# pcm2912a.net
KiCad netlist of a schematic drawn in EAGLE
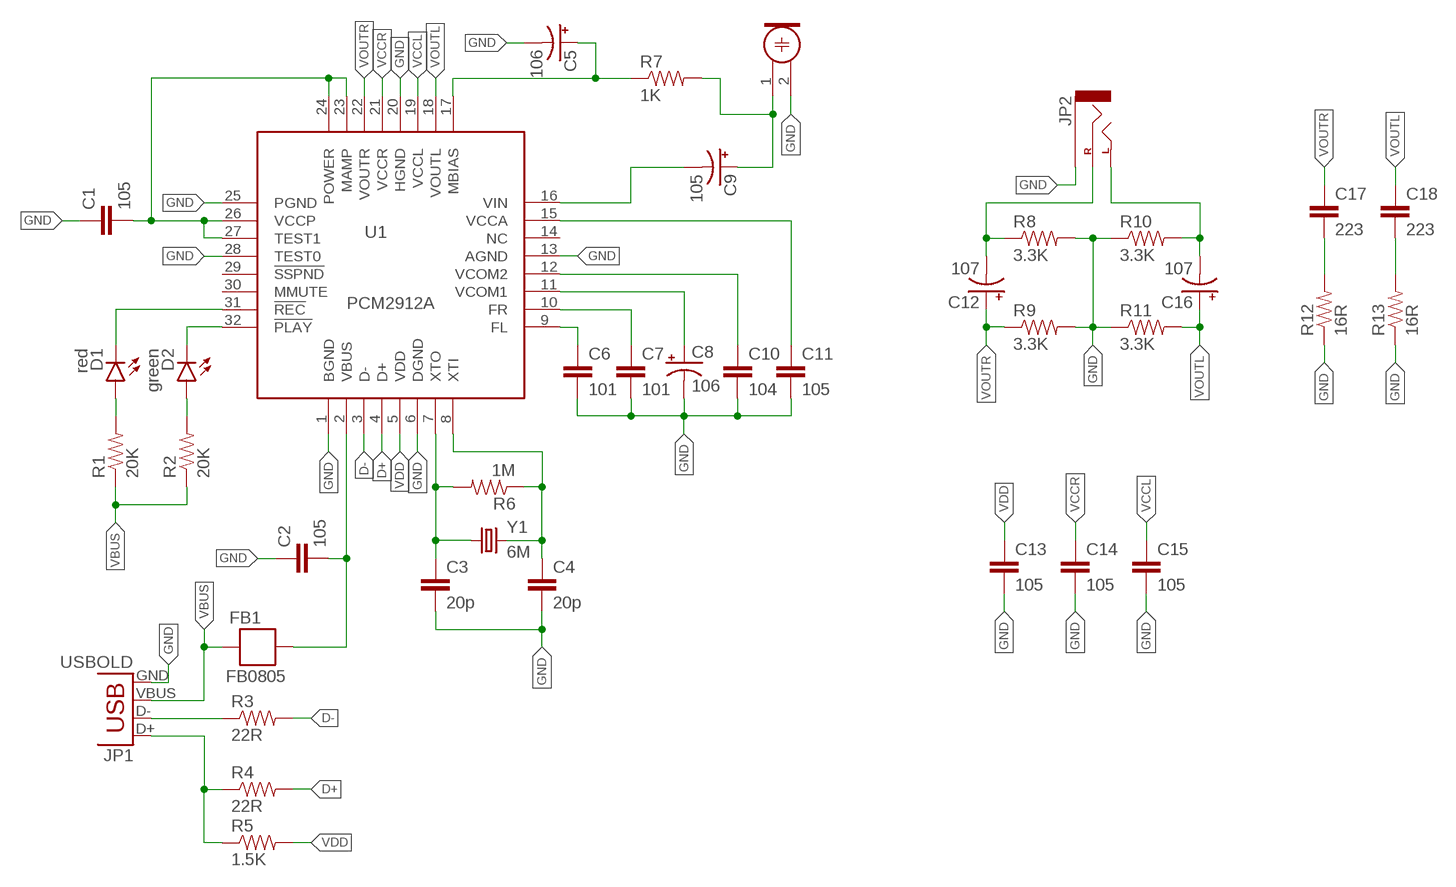
[diagram p0: schematic, sheet 1]

(export (version "E")
  (design (tool "Eeschema 10.0.6"))
  (components
    (comp (ref "C1")
      (value "105")
      (footprint "eagle-import:0402-CAP")
      (libsource (lib "eagle-import") (part "CAP0402-CAP"))
    )
    (comp (ref "C2")
      (value "105")
      (footprint "eagle-import:0402-CAP")
      (libsource (lib "eagle-import") (part "CAP0402-CAP"))
    )
    (comp (ref "C3")
      (value "20p")
      (footprint "eagle-import:0402-CAP")
      (libsource (lib "eagle-import") (part "CAP0402-CAP"))
    )
    (comp (ref "C4")
      (value "20p")
      (footprint "eagle-import:0402-CAP")
      (libsource (lib "eagle-import") (part "CAP0402-CAP"))
    )
    (comp (ref "C5")
      (value "106")
      (footprint "eagle-import:EIA3216-KIT")
      (libsource (lib "eagle-import") (part "CAP_POL1206-KIT"))
    )
    (comp (ref "C6")
      (value "101")
      (footprint "eagle-import:0402-CAP")
      (libsource (lib "eagle-import") (part "CAP0402-CAP"))
    )
    (comp (ref "C7")
      (value "101")
      (footprint "eagle-import:0402-CAP")
      (libsource (lib "eagle-import") (part "CAP0402-CAP"))
    )
    (comp (ref "C8")
      (value "106")
      (footprint "eagle-import:EIA3216-KIT")
      (libsource (lib "eagle-import") (part "CAP_POL1206-KIT"))
    )
    (comp (ref "C9")
      (value "105")
      (footprint "eagle-import:EIA3216-KIT")
      (libsource (lib "eagle-import") (part "CAP_POL1206-KIT"))
    )
    (comp (ref "C10")
      (value "104")
      (footprint "eagle-import:0402-CAP")
      (libsource (lib "eagle-import") (part "CAP0402-CAP"))
    )
    (comp (ref "C11")
      (value "105")
      (footprint "eagle-import:0402-CAP")
      (libsource (lib "eagle-import") (part "CAP0402-CAP"))
    )
    (comp (ref "C12")
      (value "107")
      (footprint "eagle-import:EIA3528-KIT")
      (libsource (lib "eagle-import") (part "CAP_POL3528-KIT"))
    )
    (comp (ref "C13")
      (value "105")
      (footprint "eagle-import:0402-CAP")
      (libsource (lib "eagle-import") (part "CAP0402-CAP"))
    )
    (comp (ref "C14")
      (value "105")
      (footprint "eagle-import:0402-CAP")
      (libsource (lib "eagle-import") (part "CAP0402-CAP"))
    )
    (comp (ref "C15")
      (value "105")
      (footprint "eagle-import:0402-CAP")
      (libsource (lib "eagle-import") (part "CAP0402-CAP"))
    )
    (comp (ref "C16")
      (value "107")
      (footprint "eagle-import:EIA3528-KIT")
      (libsource (lib "eagle-import") (part "CAP_POL3528-KIT"))
    )
    (comp (ref "C17")
      (value "223")
      (footprint "eagle-import:0402-CAP")
      (libsource (lib "eagle-import") (part "CAP0402-CAP"))
    )
    (comp (ref "C18")
      (value "223")
      (footprint "eagle-import:0402-CAP")
      (libsource (lib "eagle-import") (part "CAP0402-CAP"))
    )
    (comp (ref "D1")
      (value "red")
      (footprint "eagle-import:LED-0603-EASY")
      (libsource (lib "eagle-import") (part "LED-EASY"))
    )
    (comp (ref "D2")
      (value "green")
      (footprint "eagle-import:LED-0603-EASY")
      (libsource (lib "eagle-import") (part "LED-EASY"))
    )
    (comp (ref "FB1")
      (value "FB0805")
      (footprint "eagle-import:0805")
      (libsource (lib "eagle-import") (part "FB0805"))
    )
    (comp (ref "JP1")
      (value "USBOLD")
      (footprint "eagle-import:USB-MINIB-OLD")
      (libsource (lib "eagle-import") (part "USBOLD"))
    )
    (comp (ref "JP2")
      (value "AUDIO-JACKAUDIO-JACK-3.5MM-PTH-JLC")
      (footprint "eagle-import:AUDIO-JACK-3.5MM-PTH-JLC")
      (libsource (lib "eagle-import") (part "AUDIO-JACKAUDIO-JACK-3.5MM-PTH-JLC"))
    )
    (comp (ref "M1")
      (value "ELECTRET_MICROPHON-WM-62PC/62PK")
      (footprint "eagle-import:WM-62PC_62PK")
      (libsource (lib "eagle-import") (part "ELECTRET_MICROPHON-WM-62PC/62PK"))
    )
    (comp (ref "R1")
      (value "20K")
      (footprint "eagle-import:0402-RES")
      (libsource (lib "eagle-import") (part "RESISTOR0402"))
    )
    (comp (ref "R2")
      (value "20K")
      (footprint "eagle-import:0402-RES")
      (libsource (lib "eagle-import") (part "RESISTOR0402"))
    )
    (comp (ref "R3")
      (value "22R")
      (footprint "eagle-import:0402-RES")
      (libsource (lib "eagle-import") (part "RESISTOR0402"))
    )
    (comp (ref "R4")
      (value "22R")
      (footprint "eagle-import:0402-RES")
      (libsource (lib "eagle-import") (part "RESISTOR0402"))
    )
    (comp (ref "R5")
      (value "1.5K")
      (footprint "eagle-import:0402-RES")
      (libsource (lib "eagle-import") (part "RESISTOR0402"))
    )
    (comp (ref "R6")
      (value "1M")
      (footprint "eagle-import:0402-RES")
      (libsource (lib "eagle-import") (part "RESISTOR0402"))
    )
    (comp (ref "R7")
      (value "1K")
      (footprint "eagle-import:0402-RES")
      (libsource (lib "eagle-import") (part "RESISTOR0402"))
    )
    (comp (ref "R8")
      (value "3.3K")
      (footprint "eagle-import:0402-RES")
      (libsource (lib "eagle-import") (part "RESISTOR0402"))
    )
    (comp (ref "R9")
      (value "3.3K")
      (footprint "eagle-import:0402-RES")
      (libsource (lib "eagle-import") (part "RESISTOR0402"))
    )
    (comp (ref "R10")
      (value "3.3K")
      (footprint "eagle-import:0402-RES")
      (libsource (lib "eagle-import") (part "RESISTOR0402"))
    )
    (comp (ref "R11")
      (value "3.3K")
      (footprint "eagle-import:0402-RES")
      (libsource (lib "eagle-import") (part "RESISTOR0402"))
    )
    (comp (ref "R12")
      (value "16R")
      (footprint "eagle-import:0402-RES")
      (libsource (lib "eagle-import") (part "RESISTOR0402"))
    )
    (comp (ref "R13")
      (value "16R")
      (footprint "eagle-import:0402-RES")
      (libsource (lib "eagle-import") (part "RESISTOR0402"))
    )
    (comp (ref "U1")
      (value "PCM2912A")
      (footprint "eagle-import:TQFP32-08")
      (libsource (lib "eagle-import") (part "PCM2912A"))
    )
    (comp (ref "Y1")
      (value "6M")
      (footprint "eagle-import:HC49US")
      (libsource (lib "eagle-import") (part "CRYSTALHC49US"))
    )
  )
  (nets
    (net (code "1") (name "D+") (class "Default")
      (node (ref "R4") (pin "2") (pinfunction "2_2") (pintype "passive"))
      (node (ref "U1") (pin "4") (pinfunction "D+_4") (pintype "bidirectional"))
    )
    (net (code "2") (name "D-") (class "Default")
      (node (ref "R3") (pin "2") (pinfunction "2_2") (pintype "passive"))
      (node (ref "U1") (pin "3") (pinfunction "D-_3") (pintype "bidirectional"))
    )
    (net (code "3") (name "GND") (class "Default")
      (node (ref "C1") (pin "1") (pinfunction "1_1") (pintype "passive"))
      (node (ref "C10") (pin "2") (pinfunction "2_2") (pintype "passive"))
      (node (ref "C11") (pin "2") (pinfunction "2_2") (pintype "passive"))
      (node (ref "C13") (pin "2") (pinfunction "2_2") (pintype "passive"))
      (node (ref "C14") (pin "2") (pinfunction "2_2") (pintype "passive"))
      (node (ref "C15") (pin "2") (pinfunction "2_2") (pintype "passive"))
      (node (ref "C2") (pin "1") (pinfunction "1_1") (pintype "passive"))
      (node (ref "C3") (pin "2") (pinfunction "2_2") (pintype "passive"))
      (node (ref "C4") (pin "2") (pinfunction "2_2") (pintype "passive"))
      (node (ref "C5") (pin "C") (pinfunction "-_C") (pintype "passive"))
      (node (ref "C6") (pin "2") (pinfunction "2_2") (pintype "passive"))
      (node (ref "C7") (pin "2") (pinfunction "2_2") (pintype "passive"))
      (node (ref "C8") (pin "C") (pinfunction "-_C") (pintype "passive"))
      (node (ref "JP1") (pin "GND") (pinfunction "GND_GND") (pintype "bidirectional"))
      (node (ref "JP2") (pin "P$1") (pinfunction "SLEEVE_P$1") (pintype "bidirectional"))
      (node (ref "M1") (pin "2") (pinfunction "2_2") (pintype "passive"))
      (node (ref "R10") (pin "1") (pinfunction "1_1") (pintype "passive"))
      (node (ref "R11") (pin "1") (pinfunction "1_1") (pintype "passive"))
      (node (ref "R12") (pin "1") (pinfunction "1_1") (pintype "passive"))
      (node (ref "R13") (pin "1") (pinfunction "1_1") (pintype "passive"))
      (node (ref "R8") (pin "2") (pinfunction "2_2") (pintype "passive"))
      (node (ref "R9") (pin "2") (pinfunction "2_2") (pintype "passive"))
      (node (ref "U1") (pin "1") (pinfunction "BGND_1") (pintype "bidirectional"))
      (node (ref "U1") (pin "13") (pinfunction "AGND_13") (pintype "bidirectional"))
      (node (ref "U1") (pin "20") (pinfunction "HGND_20") (pintype "bidirectional"))
      (node (ref "U1") (pin "25") (pinfunction "PGND_25") (pintype "bidirectional"))
      (node (ref "U1") (pin "28") (pinfunction "TEST0_28") (pintype "bidirectional"))
      (node (ref "U1") (pin "6") (pinfunction "DGND_6") (pintype "bidirectional"))
    )
    (net (code "4") (name "Net-(C5-+)") (class "Default")
      (node (ref "C5") (pin "A") (pinfunction "+_A") (pintype "passive"))
      (node (ref "R7") (pin "1") (pinfunction "1_1") (pintype "passive"))
      (node (ref "U1") (pin "17") (pinfunction "MBIAS_17") (pintype "bidirectional"))
    )
    (net (code "5") (name "Net-(C8-+)") (class "Default")
      (node (ref "C8") (pin "A") (pinfunction "+_A") (pintype "passive"))
      (node (ref "U1") (pin "11") (pinfunction "VCOM1_11") (pintype "bidirectional"))
    )
    (net (code "6") (name "Net-(C9-+)") (class "Default")
      (node (ref "C9") (pin "A") (pinfunction "+_A") (pintype "passive"))
      (node (ref "M1") (pin "1") (pinfunction "1_1") (pintype "passive"))
      (node (ref "R7") (pin "2") (pinfunction "2_2") (pintype "passive"))
    )
    (net (code "7") (name "Net-(C9--)") (class "Default")
      (node (ref "C9") (pin "C") (pinfunction "-_C") (pintype "passive"))
      (node (ref "U1") (pin "16") (pinfunction "VIN_16") (pintype "bidirectional"))
    )
    (net (code "8") (name "Net-(C12--)") (class "Default")
      (node (ref "C12") (pin "C") (pinfunction "-_C") (pintype "passive"))
      (node (ref "JP2") (pin "P$2") (pinfunction "RIGHT_P$2") (pintype "bidirectional"))
      (node (ref "R8") (pin "1") (pinfunction "1_1") (pintype "passive"))
    )
    (net (code "9") (name "Net-(C16--)") (class "Default")
      (node (ref "C16") (pin "C") (pinfunction "-_C") (pintype "passive"))
      (node (ref "JP2") (pin "P$3") (pinfunction "LEFT_P$3") (pintype "bidirectional"))
      (node (ref "R10") (pin "2") (pinfunction "2_2") (pintype "passive"))
    )
    (net (code "10") (name "Net-(C17-Pad2)") (class "Default")
      (node (ref "C17") (pin "2") (pinfunction "2_2") (pintype "passive"))
      (node (ref "R12") (pin "2") (pinfunction "2_2") (pintype "passive"))
    )
    (net (code "11") (name "Net-(C18-Pad2)") (class "Default")
      (node (ref "C18") (pin "2") (pinfunction "2_2") (pintype "passive"))
      (node (ref "R13") (pin "2") (pinfunction "2_2") (pintype "passive"))
    )
    (net (code "12") (name "Net-(D1-A)") (class "Default")
      (node (ref "D1") (pin "+") (pinfunction "A_+") (pintype "passive"))
      (node (ref "R1") (pin "2") (pinfunction "2_2") (pintype "passive"))
    )
    (net (code "13") (name "Net-(D1-C)") (class "Default")
      (node (ref "D1") (pin "-") (pinfunction "C_-") (pintype "passive"))
      (node (ref "U1") (pin "31") (pinfunction "~{REC}_31") (pintype "bidirectional"))
    )
    (net (code "14") (name "Net-(D2-A)") (class "Default")
      (node (ref "D2") (pin "+") (pinfunction "A_+") (pintype "passive"))
      (node (ref "R2") (pin "2") (pinfunction "2_2") (pintype "passive"))
    )
    (net (code "15") (name "Net-(D2-C)") (class "Default")
      (node (ref "D2") (pin "-") (pinfunction "C_-") (pintype "passive"))
      (node (ref "U1") (pin "32") (pinfunction "~{PLAY}_32") (pintype "bidirectional"))
    )
    (net (code "16") (name "Net-(FB1-P$1)") (class "Default")
      (node (ref "C2") (pin "2") (pinfunction "2_2") (pintype "passive"))
      (node (ref "FB1") (pin "1") (pinfunction "P$1_1") (pintype "bidirectional"))
      (node (ref "U1") (pin "2") (pinfunction "VBUS_2") (pintype "bidirectional"))
    )
    (net (code "17") (name "Net-(JP1-PadD+)") (class "Default")
      (node (ref "JP1") (pin "D+") (pinfunction "D+_D+") (pintype "bidirectional"))
      (node (ref "R4") (pin "1") (pinfunction "1_1") (pintype "passive"))
      (node (ref "R5") (pin "1") (pinfunction "1_1") (pintype "passive"))
    )
    (net (code "18") (name "Net-(JP1-PadD-)") (class "Default")
      (node (ref "JP1") (pin "D-") (pinfunction "D-_D-") (pintype "bidirectional"))
      (node (ref "R3") (pin "1") (pinfunction "1_1") (pintype "passive"))
    )
    (net (code "19") (name "Net-(U1-FL)") (class "Default")
      (node (ref "C6") (pin "1") (pinfunction "1_1") (pintype "passive"))
      (node (ref "U1") (pin "9") (pinfunction "FL_9") (pintype "bidirectional"))
    )
    (net (code "20") (name "Net-(U1-FR)") (class "Default")
      (node (ref "C7") (pin "1") (pinfunction "1_1") (pintype "passive"))
      (node (ref "U1") (pin "10") (pinfunction "FR_10") (pintype "bidirectional"))
    )
    (net (code "21") (name "Net-(U1-MAMP)") (class "Default")
      (node (ref "C1") (pin "2") (pinfunction "2_2") (pintype "passive"))
      (node (ref "U1") (pin "23") (pinfunction "MAMP_23") (pintype "bidirectional"))
      (node (ref "U1") (pin "24") (pinfunction "POWER_24") (pintype "bidirectional"))
      (node (ref "U1") (pin "26") (pinfunction "VCCP_26") (pintype "bidirectional"))
      (node (ref "U1") (pin "27") (pinfunction "TEST1_27") (pintype "bidirectional"))
    )
    (net (code "22") (name "Net-(U1-VCCA)") (class "Default")
      (node (ref "C11") (pin "1") (pinfunction "1_1") (pintype "passive"))
      (node (ref "U1") (pin "15") (pinfunction "VCCA_15") (pintype "bidirectional"))
    )
    (net (code "23") (name "Net-(U1-VCOM2)") (class "Default")
      (node (ref "C10") (pin "1") (pinfunction "1_1") (pintype "passive"))
      (node (ref "U1") (pin "12") (pinfunction "VCOM2_12") (pintype "bidirectional"))
    )
    (net (code "24") (name "Net-(U1-XTI)") (class "Default")
      (node (ref "C4") (pin "1") (pinfunction "1_1") (pintype "passive"))
      (node (ref "R6") (pin "1") (pinfunction "1_1") (pintype "passive"))
      (node (ref "U1") (pin "8") (pinfunction "XTI_8") (pintype "bidirectional"))
      (node (ref "Y1") (pin "2") (pinfunction "2_2") (pintype "passive"))
    )
    (net (code "25") (name "Net-(U1-XTO)") (class "Default")
      (node (ref "C3") (pin "1") (pinfunction "1_1") (pintype "passive"))
      (node (ref "R6") (pin "2") (pinfunction "2_2") (pintype "passive"))
      (node (ref "U1") (pin "7") (pinfunction "XTO_7") (pintype "bidirectional"))
      (node (ref "Y1") (pin "1") (pinfunction "1_1") (pintype "passive"))
    )
    (net (code "26") (name "VBUS") (class "Default")
      (node (ref "FB1") (pin "2") (pinfunction "P$2_2") (pintype "bidirectional"))
      (node (ref "JP1") (pin "VBUS") (pinfunction "VBUS_VBUS") (pintype "bidirectional"))
      (node (ref "R1") (pin "1") (pinfunction "1_1") (pintype "passive"))
      (node (ref "R2") (pin "1") (pinfunction "1_1") (pintype "passive"))
    )
    (net (code "27") (name "VCCL") (class "Default")
      (node (ref "C15") (pin "1") (pinfunction "1_1") (pintype "passive"))
      (node (ref "U1") (pin "19") (pinfunction "VCCL_19") (pintype "bidirectional"))
    )
    (net (code "28") (name "VCCR") (class "Default")
      (node (ref "C14") (pin "1") (pinfunction "1_1") (pintype "passive"))
      (node (ref "U1") (pin "21") (pinfunction "VCCR_21") (pintype "bidirectional"))
    )
    (net (code "29") (name "VDD") (class "Default")
      (node (ref "C13") (pin "1") (pinfunction "1_1") (pintype "passive"))
      (node (ref "R5") (pin "2") (pinfunction "2_2") (pintype "passive"))
      (node (ref "U1") (pin "5") (pinfunction "VDD_5") (pintype "bidirectional"))
    )
    (net (code "30") (name "VOUTL") (class "Default")
      (node (ref "C16") (pin "A") (pinfunction "+_A") (pintype "passive"))
      (node (ref "C18") (pin "1") (pinfunction "1_1") (pintype "passive"))
      (node (ref "R11") (pin "2") (pinfunction "2_2") (pintype "passive"))
      (node (ref "U1") (pin "18") (pinfunction "VOUTL_18") (pintype "bidirectional"))
    )
    (net (code "31") (name "VOUTR") (class "Default")
      (node (ref "C12") (pin "A") (pinfunction "+_A") (pintype "passive"))
      (node (ref "C17") (pin "1") (pinfunction "1_1") (pintype "passive"))
      (node (ref "R9") (pin "1") (pinfunction "1_1") (pintype "passive"))
      (node (ref "U1") (pin "22") (pinfunction "VOUTR_22") (pintype "bidirectional"))
    )
    (net (code "32") (name "unconnected-(U1-MMUTE-Pad30)") (class "Default")
      (node (ref "U1") (pin "30") (pinfunction "MMUTE_30") (pintype "bidirectional"))
    )
    (net (code "33") (name "unconnected-(U1-NC-Pad14)") (class "Default")
      (node (ref "U1") (pin "14") (pinfunction "NC_14") (pintype "bidirectional"))
    )
    (net (code "34") (name "unconnected-(U1-~{SSPND}-Pad29)") (class "Default")
      (node (ref "U1") (pin "29") (pinfunction "~{SSPND}_29") (pintype "bidirectional"))
    )
  )
)
